# VSSOP-10_breakout.net
KiCad netlist of a schematic drawn in EAGLE
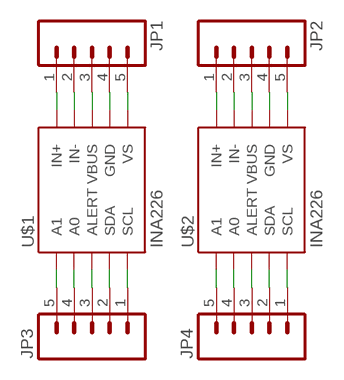
[diagram p0: schematic, sheet 1]

(export (version "E")
  (design (tool "Eeschema 10.0.6"))
  (components
    (comp (ref "JP1")
      (value "M05")
      (footprint "eagle-import:1X05")
      (libsource (lib "eagle-import") (part "M05"))
    )
    (comp (ref "JP2")
      (value "M05")
      (footprint "eagle-import:1X05")
      (libsource (lib "eagle-import") (part "M05"))
    )
    (comp (ref "JP3")
      (value "M05")
      (footprint "eagle-import:1X05")
      (libsource (lib "eagle-import") (part "M05"))
    )
    (comp (ref "JP4")
      (value "M05")
      (footprint "eagle-import:1X05")
      (libsource (lib "eagle-import") (part "M05"))
    )
    (comp (ref "U$1")
      (value "INA226")
      (footprint "eagle-import:VSSOP-10")
      (libsource (lib "eagle-import") (part "INA226"))
    )
    (comp (ref "U$2")
      (value "INA226")
      (footprint "eagle-import:VSSOP-10")
      (libsource (lib "eagle-import") (part "INA226"))
    )
  )
  (nets
    (net (code "1") (name "Net-(U$1-A0)") (class "Default")
      (node (ref "JP3") (pin "4") (pinfunction "4_4") (pintype "passive"))
      (node (ref "U$1") (pin "2") (pinfunction "A0_2") (pintype "passive"))
    )
    (net (code "2") (name "Net-(U$1-A1)") (class "Default")
      (node (ref "JP3") (pin "5") (pinfunction "5_5") (pintype "passive"))
      (node (ref "U$1") (pin "1") (pinfunction "A1_1") (pintype "passive"))
    )
    (net (code "3") (name "Net-(U$1-ALERT)") (class "Default")
      (node (ref "JP3") (pin "3") (pinfunction "3_3") (pintype "passive"))
      (node (ref "U$1") (pin "3") (pinfunction "ALERT_3") (pintype "passive"))
    )
    (net (code "4") (name "Net-(U$1-GND)") (class "Default")
      (node (ref "JP1") (pin "4") (pinfunction "4_4") (pintype "passive"))
      (node (ref "U$1") (pin "7") (pinfunction "GND_7") (pintype "passive"))
    )
    (net (code "5") (name "Net-(U$1-IN+)") (class "Default")
      (node (ref "JP1") (pin "1") (pinfunction "1_1") (pintype "passive"))
      (node (ref "U$1") (pin "10") (pinfunction "IN+_10") (pintype "passive"))
    )
    (net (code "6") (name "Net-(U$1-IN-)") (class "Default")
      (node (ref "JP1") (pin "2") (pinfunction "2_2") (pintype "passive"))
      (node (ref "U$1") (pin "9") (pinfunction "IN-_9") (pintype "passive"))
    )
    (net (code "7") (name "Net-(U$1-SCL)") (class "Default")
      (node (ref "JP3") (pin "1") (pinfunction "1_1") (pintype "passive"))
      (node (ref "U$1") (pin "5") (pinfunction "SCL_5") (pintype "passive"))
    )
    (net (code "8") (name "Net-(U$1-SDA)") (class "Default")
      (node (ref "JP3") (pin "2") (pinfunction "2_2") (pintype "passive"))
      (node (ref "U$1") (pin "4") (pinfunction "SDA_4") (pintype "passive"))
    )
    (net (code "9") (name "Net-(U$1-VBUS)") (class "Default")
      (node (ref "JP1") (pin "3") (pinfunction "3_3") (pintype "passive"))
      (node (ref "U$1") (pin "8") (pinfunction "VBUS_8") (pintype "passive"))
    )
    (net (code "10") (name "Net-(U$1-VS)") (class "Default")
      (node (ref "JP1") (pin "5") (pinfunction "5_5") (pintype "passive"))
      (node (ref "U$1") (pin "6") (pinfunction "VS_6") (pintype "passive"))
    )
    (net (code "11") (name "Net-(U$2-A0)") (class "Default")
      (node (ref "JP4") (pin "4") (pinfunction "4_4") (pintype "passive"))
      (node (ref "U$2") (pin "2") (pinfunction "A0_2") (pintype "passive"))
    )
    (net (code "12") (name "Net-(U$2-A1)") (class "Default")
      (node (ref "JP4") (pin "5") (pinfunction "5_5") (pintype "passive"))
      (node (ref "U$2") (pin "1") (pinfunction "A1_1") (pintype "passive"))
    )
    (net (code "13") (name "Net-(U$2-ALERT)") (class "Default")
      (node (ref "JP4") (pin "3") (pinfunction "3_3") (pintype "passive"))
      (node (ref "U$2") (pin "3") (pinfunction "ALERT_3") (pintype "passive"))
    )
    (net (code "14") (name "Net-(U$2-GND)") (class "Default")
      (node (ref "JP2") (pin "4") (pinfunction "4_4") (pintype "passive"))
      (node (ref "U$2") (pin "7") (pinfunction "GND_7") (pintype "passive"))
    )
    (net (code "15") (name "Net-(U$2-IN+)") (class "Default")
      (node (ref "JP2") (pin "1") (pinfunction "1_1") (pintype "passive"))
      (node (ref "U$2") (pin "10") (pinfunction "IN+_10") (pintype "passive"))
    )
    (net (code "16") (name "Net-(U$2-IN-)") (class "Default")
      (node (ref "JP2") (pin "2") (pinfunction "2_2") (pintype "passive"))
      (node (ref "U$2") (pin "9") (pinfunction "IN-_9") (pintype "passive"))
    )
    (net (code "17") (name "Net-(U$2-SCL)") (class "Default")
      (node (ref "JP4") (pin "1") (pinfunction "1_1") (pintype "passive"))
      (node (ref "U$2") (pin "5") (pinfunction "SCL_5") (pintype "passive"))
    )
    (net (code "18") (name "Net-(U$2-SDA)") (class "Default")
      (node (ref "JP4") (pin "2") (pinfunction "2_2") (pintype "passive"))
      (node (ref "U$2") (pin "4") (pinfunction "SDA_4") (pintype "passive"))
    )
    (net (code "19") (name "Net-(U$2-VBUS)") (class "Default")
      (node (ref "JP2") (pin "3") (pinfunction "3_3") (pintype "passive"))
      (node (ref "U$2") (pin "8") (pinfunction "VBUS_8") (pintype "passive"))
    )
    (net (code "20") (name "Net-(U$2-VS)") (class "Default")
      (node (ref "JP2") (pin "5") (pinfunction "5_5") (pintype "passive"))
      (node (ref "U$2") (pin "6") (pinfunction "VS_6") (pintype "passive"))
    )
  )
)
